# eletric.net
KiCad netlist of a schematic drawn in EAGLE
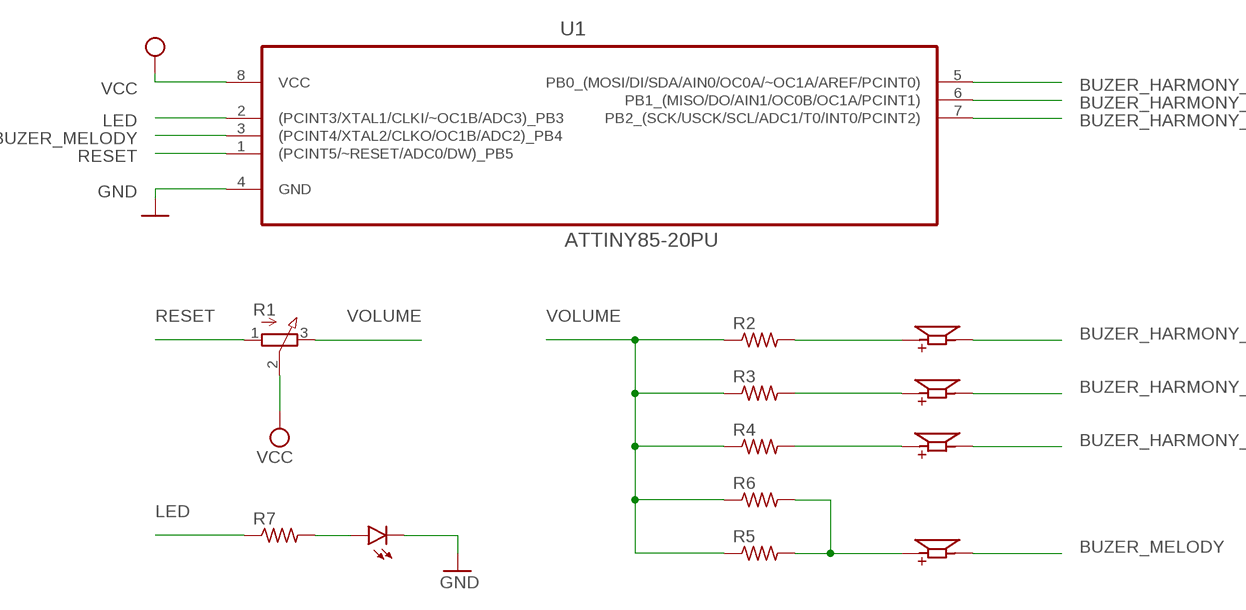
[diagram p0: schematic, sheet 1]

(export (version "E")
  (design (tool "Eeschema 10.0.6"))
  (components
    (comp (ref "LED2")
      (value "LED5MM")
      (footprint "eagle-import:LED5MM")
      (libsource (lib "eagle-import") (part "LED5MM"))
    )
    (comp (ref "LS1")
      (value "CMT-8530S-SMT")
      (footprint "eagle-import:CUI_CMT-8530S-SMT")
      (fields (field (name "MF") "CUI Devices") (field (name "MP") "CMT-8530S-SMT-TR"))
      (libsource (lib "eagle-import") (part "CMT-8530S-SMT"))
    )
    (comp (ref "LS2")
      (value "CMT-8530S-SMT")
      (footprint "eagle-import:CUI_CMT-8530S-SMT")
      (fields (field (name "MF") "CUI Devices") (field (name "MP") "CMT-8530S-SMT-TR"))
      (libsource (lib "eagle-import") (part "CMT-8530S-SMT"))
    )
    (comp (ref "LS3")
      (value "CMT-8530S-SMT")
      (footprint "eagle-import:CUI_CMT-8530S-SMT")
      (fields (field (name "MF") "CUI Devices") (field (name "MP") "CMT-8530S-SMT-TR"))
      (libsource (lib "eagle-import") (part "CMT-8530S-SMT"))
    )
    (comp (ref "LS4")
      (value "CMT-8530S-SMT")
      (footprint "eagle-import:CUI_CMT-8530S-SMT")
      (fields (field (name "MF") "CUI Devices") (field (name "MP") "CMT-8530S-SMT-TR"))
      (libsource (lib "eagle-import") (part "CMT-8530S-SMT"))
    )
    (comp (ref "R1")
      (value "3RP/1610N")
      (footprint "eagle-import:3RP_1610N")
      (libsource (lib "eagle-import") (part "3RP/1610N"))
    )
    (comp (ref "R2")
      (value "R-US_R0805")
      (footprint "eagle-import:R0805")
      (libsource (lib "eagle-import") (part "R-US_R0805"))
    )
    (comp (ref "R3")
      (value "R-US_R0805")
      (footprint "eagle-import:R0805")
      (libsource (lib "eagle-import") (part "R-US_R0805"))
    )
    (comp (ref "R4")
      (value "R-US_R0805")
      (footprint "eagle-import:R0805")
      (libsource (lib "eagle-import") (part "R-US_R0805"))
    )
    (comp (ref "R5")
      (value "R-US_R0805")
      (footprint "eagle-import:R0805")
      (libsource (lib "eagle-import") (part "R-US_R0805"))
    )
    (comp (ref "R6")
      (value "R-US_R0805")
      (footprint "eagle-import:R0805")
      (libsource (lib "eagle-import") (part "R-US_R0805"))
    )
    (comp (ref "R7")
      (value "R-US_R0805")
      (footprint "eagle-import:R0805")
      (libsource (lib "eagle-import") (part "R-US_R0805"))
    )
    (comp (ref "U1")
      (value "ATTINY85-20PU")
      (footprint "eagle-import:DIP254P762X533-8")
      (fields (field (name "MF") "Microchip"))
      (libsource (lib "eagle-import") (part "ATTINY85-20PU"))
    )
  )
  (nets
    (net (code "1") (name "/BUZER_HARMONY_1") (class "Default")
      (node (ref "LS2") (pin "N") (pinfunction "N_N") (pintype "passive"))
      (node (ref "U1") (pin "7") (pinfunction "PB2_(SCK/USCK/SCL/ADC1/T0/INT0/PCINT2)_7") (pintype "bidirectional"))
    )
    (net (code "2") (name "/BUZER_HARMONY_2") (class "Default")
      (node (ref "LS4") (pin "N") (pinfunction "N_N") (pintype "passive"))
      (node (ref "U1") (pin "6") (pinfunction "PB1_(MISO/DO/AIN1/OC0B/OC1A/PCINT1)_6") (pintype "bidirectional"))
    )
    (net (code "3") (name "/BUZER_HARMONY_3") (class "Default")
      (node (ref "LS3") (pin "N") (pinfunction "N_N") (pintype "passive"))
      (node (ref "U1") (pin "5") (pinfunction "PB0_(MOSI/DI/SDA/AIN0/OC0A/~{OC1A/AREF/PCINT0})_5") (pintype "bidirectional"))
    )
    (net (code "4") (name "/BUZER_MELODY") (class "Default")
      (node (ref "LS1") (pin "N") (pinfunction "N_N") (pintype "passive"))
      (node (ref "U1") (pin "3") (pinfunction "(PCINT4/XTAL2/CLKO/OC1B/ADC2)_PB4_3") (pintype "bidirectional"))
    )
    (net (code "5") (name "/LED") (class "Default")
      (node (ref "R7") (pin "1") (pinfunction "1_1") (pintype "passive"))
      (node (ref "U1") (pin "2") (pinfunction "(PCINT3/XTAL1/CLKI/~{OC1B/ADC3})_PB3_2") (pintype "bidirectional"))
    )
    (net (code "6") (name "/RESET") (class "Default")
      (node (ref "R1") (pin "1") (pinfunction "A_1") (pintype "passive"))
      (node (ref "U1") (pin "1") (pinfunction "(PCINT5/~{RESET/ADC0/DW})_PB5_1") (pintype "bidirectional"))
    )
    (net (code "7") (name "/VOLUME") (class "Default")
      (node (ref "R1") (pin "3") (pinfunction "E_3") (pintype "passive"))
      (node (ref "R2") (pin "1") (pinfunction "1_1") (pintype "passive"))
      (node (ref "R3") (pin "1") (pinfunction "1_1") (pintype "passive"))
      (node (ref "R4") (pin "1") (pinfunction "1_1") (pintype "passive"))
      (node (ref "R5") (pin "1") (pinfunction "1_1") (pintype "passive"))
      (node (ref "R6") (pin "1") (pinfunction "1_1") (pintype "passive"))
    )
    (net (code "8") (name "GND") (class "Default")
      (node (ref "LED2") (pin "K") (pinfunction "C_K") (pintype "passive"))
      (node (ref "U1") (pin "4") (pinfunction "GND_4") (pintype "passive"))
    )
    (net (code "9") (name "Net-(LED2-PadA)") (class "Default")
      (node (ref "LED2") (pin "A") (pinfunction "A_A") (pintype "passive"))
      (node (ref "R7") (pin "2") (pinfunction "2_2") (pintype "passive"))
    )
    (net (code "10") (name "Net-(LS1-PadP)") (class "Default")
      (node (ref "LS1") (pin "P") (pinfunction "P_P") (pintype "passive"))
      (node (ref "R5") (pin "2") (pinfunction "2_2") (pintype "passive"))
      (node (ref "R6") (pin "2") (pinfunction "2_2") (pintype "passive"))
    )
    (net (code "11") (name "Net-(LS2-PadP)") (class "Default")
      (node (ref "LS2") (pin "P") (pinfunction "P_P") (pintype "passive"))
      (node (ref "R2") (pin "2") (pinfunction "2_2") (pintype "passive"))
    )
    (net (code "12") (name "Net-(LS3-PadP)") (class "Default")
      (node (ref "LS3") (pin "P") (pinfunction "P_P") (pintype "passive"))
      (node (ref "R4") (pin "2") (pinfunction "2_2") (pintype "passive"))
    )
    (net (code "13") (name "Net-(LS4-PadP)") (class "Default")
      (node (ref "LS4") (pin "P") (pinfunction "P_P") (pintype "passive"))
      (node (ref "R3") (pin "2") (pinfunction "2_2") (pintype "passive"))
    )
    (net (code "14") (name "VCC") (class "Default")
      (node (ref "R1") (pin "2") (pinfunction "S_2") (pintype "passive"))
      (node (ref "U1") (pin "8") (pinfunction "VCC_8") (pintype "power_in"))
    )
  )
)
